# Sheet2.net
KiCad netlist of a schematic drawn in Altium Designer
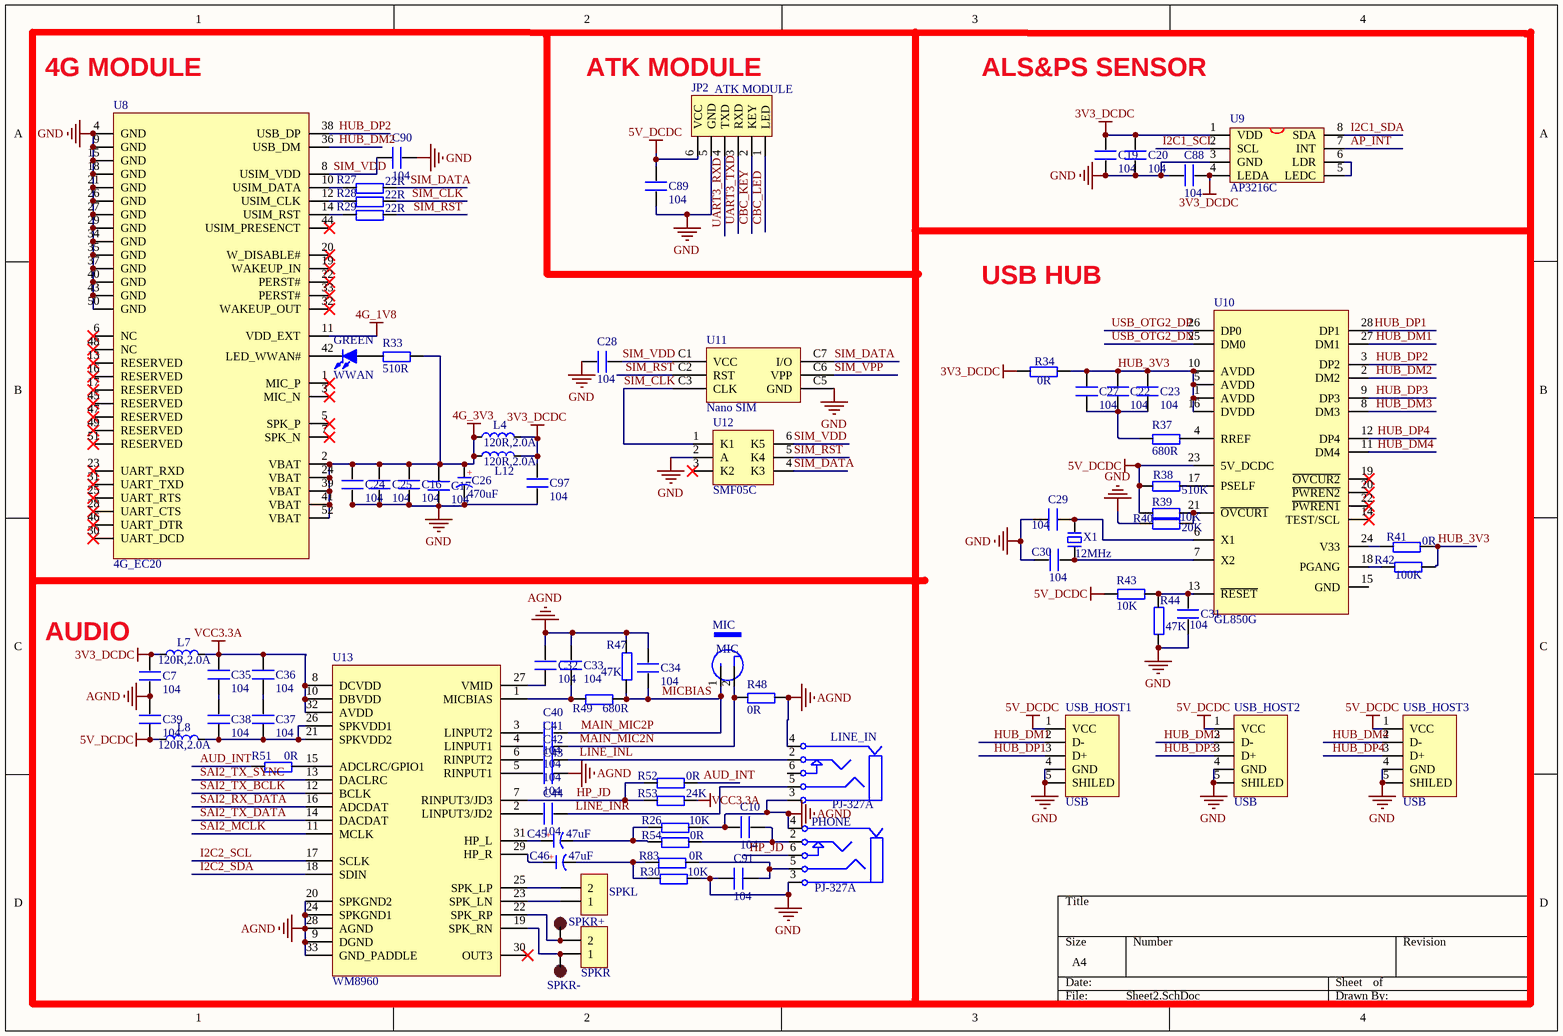
[diagram p0: Sheet2.SchDoc]

(export (version "E")
  (design (tool "Eeschema 10.0.6"))
  (components
    (comp (ref "C7") (value "104") (footprint "C 0603") (libsource (lib "linux_board_SCH") (part "C")))
    (comp (ref "C10") (value "104") (footprint "C 0603") (libsource (lib "linux_board_SCH") (part "C")))
    (comp (ref "C16") (value "104") (footprint "C 0603") (libsource (lib "linux_board_SCH") (part "C")))
    (comp (ref "C17") (value "104") (footprint "C 0603") (libsource (lib "linux_board_SCH") (part "C")))
    (comp (ref "C19") (value "104") (footprint "C 0603") (libsource (lib "linux_board_SCH") (part "C")))
    (comp (ref "C20") (value "104") (footprint "C 0603") (libsource (lib "linux_board_SCH") (part "C")))
    (comp (ref "C22") (value "104") (footprint "C 0603") (libsource (lib "linux_board_SCH") (part "C")))
    (comp (ref "C23") (value "104") (footprint "C 0603") (libsource (lib "linux_board_SCH") (part "C")))
    (comp (ref "C24") (value "104") (footprint "C 0603") (libsource (lib "linux_board_SCH") (part "C")))
    (comp (ref "C25") (value "104") (footprint "C 0603") (libsource (lib "linux_board_SCH") (part "C")))
    (comp (ref "C26")
      (value "470uF")
      (footprint "CM D(6.3*5.4)")
      (description "贴片电解电容")
      (fields (field (name "版权归属") "源创客"))
      (libsource (lib "linux_board_SCH") (part "C-CM"))
    )
    (comp (ref "C27") (value "104") (footprint "C 0603") (libsource (lib "linux_board_SCH") (part "C")))
    (comp (ref "C28") (value "104") (footprint "C 0603") (libsource (lib "linux_board_SCH") (part "C")))
    (comp (ref "C29") (value "104") (footprint "C 0603") (libsource (lib "linux_board_SCH") (part "C")))
    (comp (ref "C30") (value "104") (footprint "C 0603") (libsource (lib "linux_board_SCH") (part "C")))
    (comp (ref "C31") (value "104") (footprint "C 0603") (libsource (lib "linux_board_SCH") (part "C")))
    (comp (ref "C32") (value "104") (footprint "C 0603") (libsource (lib "linux_board_SCH") (part "C")))
    (comp (ref "C33") (value "104") (footprint "C 0603") (libsource (lib "linux_board_SCH") (part "C")))
    (comp (ref "C34") (value "104") (footprint "C 0603") (libsource (lib "linux_board_SCH") (part "C")))
    (comp (ref "C35") (value "104") (footprint "C 0603") (libsource (lib "linux_board_SCH") (part "C")))
    (comp (ref "C36") (value "104") (footprint "C 0603") (libsource (lib "linux_board_SCH") (part "C")))
    (comp (ref "C37") (value "104") (footprint "C 0603") (libsource (lib "linux_board_SCH") (part "C")))
    (comp (ref "C38") (value "104") (footprint "C 0603") (libsource (lib "linux_board_SCH") (part "C")))
    (comp (ref "C39") (value "104") (footprint "C 0603") (libsource (lib "linux_board_SCH") (part "C")))
    (comp (ref "C40") (value "104") (footprint "C 0603") (libsource (lib "linux_board_SCH") (part "C")))
    (comp (ref "C41") (value "104") (footprint "C 0603") (libsource (lib "linux_board_SCH") (part "C")))
    (comp (ref "C42") (value "104") (footprint "C 0603") (libsource (lib "linux_board_SCH") (part "C")))
    (comp (ref "C43") (value "104") (footprint "C 0603") (libsource (lib "linux_board_SCH") (part "C")))
    (comp (ref "C44") (value "104") (footprint "C 0603") (libsource (lib "linux_board_SCH") (part "C")))
    (comp (ref "C45")
      (value "47uF")
      (footprint "CM D(6.3*5.4)")
      (description "贴片电解电容")
      (fields (field (name "版权归属") "源创客"))
      (libsource (lib "") (part "C-CM_1"))
    )
    (comp (ref "C46")
      (value "47uF")
      (footprint "CM D(6.3*5.4)")
      (description "贴片电解电容")
      (fields (field (name "版权归属") "源创客"))
      (libsource (lib "") (part "C-CM_1"))
    )
    (comp (ref "C88") (value "104") (footprint "C 0603") (libsource (lib "linux_board_SCH") (part "C")))
    (comp (ref "C89") (value "104") (footprint "C 0603") (libsource (lib "linux_board_SCH") (part "C")))
    (comp (ref "C90") (value "104") (footprint "C 0603") (libsource (lib "linux_board_SCH") (part "C")))
    (comp (ref "C91") (value "104") (footprint "C 0603") (libsource (lib "linux_board_SCH") (part "C")))
    (comp (ref "C97") (value "104") (footprint "C 0603") (libsource (lib "linux_board_SCH") (part "C")))
    (comp (ref "GREEN")
      (value "WWAN")
      (footprint "LED 0805R")
      (description "贴片LED")
      (fields (field (name "版权归属") "源创客"))
      (libsource (lib "linux_board_SCH") (part "LED-SMD"))
    )
    (comp (ref "JP2")
      (value "ATK MODULE")
      (footprint "HEAD6")
      (description "ATK-HC05")
      (libsource (lib "linux_board_SCH") (part "ATK-HC05"))
    )
    (comp (ref "L4")
      (value "120R,2.0A")
      (footprint "L 0603")
      (description "小功率贴片电感磁珠")
      (fields (field (name "版权归属") "源创客"))
      (libsource (lib "linux_board_SCH") (part "L"))
    )
    (comp (ref "L7")
      (value "120R,2.0A")
      (footprint "L 0603")
      (description "小功率贴片电感磁珠")
      (fields (field (name "版权归属") "源创客"))
      (libsource (lib "linux_board_SCH") (part "L"))
    )
    (comp (ref "L8")
      (value "120R,2.0A")
      (footprint "L 0603")
      (description "小功率贴片电感磁珠")
      (fields (field (name "版权归属") "源创客"))
      (libsource (lib "linux_board_SCH") (part "L"))
    )
    (comp (ref "L12")
      (value "120R,2.0A")
      (footprint "L 0603")
      (description "小功率贴片电感磁珠")
      (fields (field (name "版权归属") "源创客"))
      (libsource (lib "linux_board_SCH") (part "L"))
    )
    (comp (ref "LINE_IN")
      (value "PJ-327A")
      (footprint "PJ327A")
      (libsource (lib "linux_board_SCH") (part "PJ-327A"))
    )
    (comp (ref "MIC") (value "MIC") (footprint "MIC-6022") (libsource (lib "linux_board_SCH") (part "MIC")))
    (comp (ref "PHONE")
      (value "PJ-327A")
      (footprint "PJ327A")
      (libsource (lib "linux_board_SCH") (part "PJ-327A"))
    )
    (comp (ref "R26") (value "10K") (footprint "R 0603") (libsource (lib "linux_board_SCH") (part "R")))
    (comp (ref "R27") (value "22R") (footprint "R 0603") (libsource (lib "linux_board_SCH") (part "R")))
    (comp (ref "R28") (value "22R") (footprint "R 0603") (libsource (lib "linux_board_SCH") (part "R")))
    (comp (ref "R29") (value "22R") (footprint "R 0603") (libsource (lib "linux_board_SCH") (part "R")))
    (comp (ref "R30") (value "10K") (footprint "R 0603") (libsource (lib "linux_board_SCH") (part "R")))
    (comp (ref "R33") (value "510R") (footprint "R 0603") (libsource (lib "linux_board_SCH") (part "R")))
    (comp (ref "R34") (value "0R") (footprint "R 0603") (libsource (lib "linux_board_SCH") (part "R")))
    (comp (ref "R37") (value "680R") (footprint "R 0603") (libsource (lib "linux_board_SCH") (part "R")))
    (comp (ref "R38") (value "510K") (footprint "R 0603") (libsource (lib "linux_board_SCH") (part "R")))
    (comp (ref "R39") (value "10K") (footprint "R 0603") (libsource (lib "linux_board_SCH") (part "R")))
    (comp (ref "R40") (value "20K") (footprint "R 0603") (libsource (lib "linux_board_SCH") (part "R")))
    (comp (ref "R41") (value "0R") (footprint "R 0603") (libsource (lib "linux_board_SCH") (part "R")))
    (comp (ref "R42") (value "100K") (footprint "R 0603") (libsource (lib "linux_board_SCH") (part "R")))
    (comp (ref "R43") (value "10K") (footprint "R 0603") (libsource (lib "linux_board_SCH") (part "R")))
    (comp (ref "R44") (value "47K") (footprint "R 0603") (libsource (lib "linux_board_SCH") (part "R")))
    (comp (ref "R47") (value "47K") (footprint "R 0603") (libsource (lib "linux_board_SCH") (part "R")))
    (comp (ref "R48") (value "0R") (footprint "R 0603") (libsource (lib "linux_board_SCH") (part "R")))
    (comp (ref "R49") (value "680R") (footprint "R 0603") (libsource (lib "linux_board_SCH") (part "R")))
    (comp (ref "R51") (value "0R") (footprint "R 0603") (libsource (lib "linux_board_SCH") (part "R")))
    (comp (ref "R52") (value "0R") (footprint "R 0603") (libsource (lib "linux_board_SCH") (part "R")))
    (comp (ref "R53") (value "24K") (footprint "R 0603") (libsource (lib "linux_board_SCH") (part "R")))
    (comp (ref "R54") (value "0R") (footprint "R 0603") (libsource (lib "linux_board_SCH") (part "R")))
    (comp (ref "R83") (value "0R") (footprint "R 0603") (libsource (lib "linux_board_SCH") (part "R")))
    (comp (ref "SPKL")
      (value "SPKL")
      (footprint "XH2.54-2P_H")
      (description "2P接插件")
      (fields (field (name "版权归属") "源创客"))
      (libsource (lib "linux_board_SCH") (part "Header 2"))
    )
    (comp (ref "SPKR")
      (value "SPKL")
      (footprint "XH2.54-2P_H")
      (description "2P接插件")
      (fields (field (name "版权归属") "源创客"))
      (libsource (lib "linux_board_SCH") (part "Header 2"))
    )
    (comp (ref "SPKR+")
      (value "SPK+")
      (footprint "TP-1.5")
      (description "测试点")
      (libsource (lib "linux_board_SCH") (part "TEST-POINT"))
    )
    (comp (ref "SPKR-")
      (value "SPK+")
      (footprint "TP-1.5")
      (description "测试点")
      (libsource (lib "linux_board_SCH") (part "TEST-POINT"))
    )
    (comp (ref "U8")
      (value "4G_EC20")
      (footprint "Mini PCIE 52P")
      (libsource (lib "linux_board_SCH") (part "4G-EC20"))
    )
    (comp (ref "U9")
      (value "AP3216C")
      (footprint "QFN8")
      (description "ALS+PS Sensor")
      (libsource (lib "linux_board_SCH") (part "AP3216C"))
    )
    (comp (ref "U10")
      (value "GL850G")
      (footprint "SSOP28_L")
      (libsource (lib "linux_board_SCH") (part "GL850G"))
    )
    (comp (ref "U11")
      (value "Nano SIM")
      (footprint "Nano SIM 7P")
      (libsource (lib "linux_board_SCH") (part "Nano SIM"))
    )
    (comp (ref "U12")
      (value "SMF05C")
      (footprint "SOT363-6L")
      (libsource (lib "linux_board_SCH") (part "SMF05C"))
    )
    (comp (ref "U13")
      (value "WM8960")
      (footprint "QFN32 5x5_L")
      (libsource (lib "linux_board_SCH") (part "WM8960"))
    )
    (comp (ref "USB_HOST1")
      (value "USB")
      (footprint "USB-A/S_E")
      (description "USB-A型母接口")
      (fields (field (name "版权归属") "源创客"))
      (libsource (lib "linux_board_SCH") (part "USB-A/S"))
    )
    (comp (ref "USB_HOST2")
      (value "USB")
      (footprint "USB-A/S_E")
      (description "USB-A型母接口")
      (fields (field (name "版权归属") "源创客"))
      (libsource (lib "linux_board_SCH") (part "USB-A/S"))
    )
    (comp (ref "USB_HOST3")
      (value "USB")
      (footprint "USB-A/S_E")
      (description "USB-A型母接口")
      (fields (field (name "版权归属") "源创客"))
      (libsource (lib "linux_board_SCH") (part "USB-A/S"))
    )
    (comp (ref "X1")
      (value "12MHz")
      (footprint "XTAL-49S DIP")
      (description "2脚无源晶振")
      (fields (field (name "版权归属") "源创客"))
      (libsource (lib "linux_board_SCH") (part "XTAL-2P"))
    )
  )
  (nets
    (net (code "1") (name "/AP_INT") (class "Default")
      (node (ref "U9") (pin "7") (pinfunction "INT_7") (pintype "passive"))
    )
    (net (code "2") (name "/AUD_INT") (class "Default")
      (node (ref "R51") (pin "1") (pintype "passive"))
      (node (ref "R52") (pin "2") (pintype "passive"))
    )
    (net (code "3") (name "/CBC_KEY") (class "Default")
      (node (ref "JP2") (pin "2") (pinfunction "KEY_2") (pintype "passive"))
    )
    (net (code "4") (name "/CBC_LED") (class "Default")
      (node (ref "JP2") (pin "1") (pinfunction "LED_1") (pintype "passive"))
    )
    (net (code "5") (name "/HP_JD") (class "Default")
      (node (ref "PHONE") (pin "6") (pinfunction "6_6") (pintype "passive"))
      (node (ref "R52") (pin "1") (pintype "passive"))
      (node (ref "R53") (pin "1") (pintype "passive"))
      (node (ref "U13") (pin "7") (pinfunction "RINPUT3/JD3_7") (pintype "passive"))
    )
    (net (code "6") (name "/HUB_3V3") (class "Default")
      (node (ref "C22") (pin "2") (pinfunction "2_2") (pintype "passive"))
      (node (ref "C23") (pin "2") (pinfunction "2_2") (pintype "passive"))
      (node (ref "C27") (pin "2") (pinfunction "2_2") (pintype "passive"))
      (node (ref "R34") (pin "2") (pintype "passive"))
      (node (ref "R41") (pin "2") (pintype "passive"))
      (node (ref "R42") (pin "2") (pintype "passive"))
      (node (ref "U10") (pin "1") (pinfunction "AVDD_1") (pintype "passive"))
      (node (ref "U10") (pin "10") (pinfunction "AVDD_10") (pintype "passive"))
      (node (ref "U10") (pin "16") (pinfunction "DVDD_16") (pintype "passive"))
      (node (ref "U10") (pin "5") (pinfunction "AVDD_5") (pintype "passive"))
    )
    (net (code "7") (name "/HUB_DM1") (class "Default")
      (node (ref "U10") (pin "27") (pinfunction "DM1_27") (pintype "passive"))
      (node (ref "USB_HOST1") (pin "2") (pinfunction "D-_2") (pintype "passive"))
    )
    (net (code "8") (name "/HUB_DM2") (class "Default")
      (node (ref "U10") (pin "2") (pinfunction "DM2_2") (pintype "passive"))
      (node (ref "U8") (pin "36") (pinfunction "USB_DM_36") (pintype "passive"))
    )
    (net (code "9") (name "/HUB_DM3") (class "Default")
      (node (ref "U10") (pin "8") (pinfunction "DM3_8") (pintype "passive"))
      (node (ref "USB_HOST2") (pin "2") (pinfunction "D-_2") (pintype "passive"))
    )
    (net (code "10") (name "/HUB_DM4") (class "Default")
      (node (ref "U10") (pin "11") (pinfunction "DM4_11") (pintype "passive"))
      (node (ref "USB_HOST3") (pin "2") (pinfunction "D-_2") (pintype "passive"))
    )
    (net (code "11") (name "/HUB_DP1") (class "Default")
      (node (ref "U10") (pin "28") (pinfunction "DP1_28") (pintype "passive"))
      (node (ref "USB_HOST1") (pin "3") (pinfunction "D+_3") (pintype "passive"))
    )
    (net (code "12") (name "/HUB_DP2") (class "Default")
      (node (ref "U10") (pin "3") (pinfunction "DP2_3") (pintype "passive"))
      (node (ref "U8") (pin "38") (pinfunction "USB_DP_38") (pintype "passive"))
    )
    (net (code "13") (name "/HUB_DP3") (class "Default")
      (node (ref "U10") (pin "9") (pinfunction "DP3_9") (pintype "passive"))
      (node (ref "USB_HOST2") (pin "3") (pinfunction "D+_3") (pintype "passive"))
    )
    (net (code "14") (name "/HUB_DP4") (class "Default")
      (node (ref "U10") (pin "12") (pinfunction "DP4_12") (pintype "passive"))
      (node (ref "USB_HOST3") (pin "3") (pinfunction "D+_3") (pintype "passive"))
    )
    (net (code "15") (name "/I2C1_SCL") (class "Default")
      (node (ref "U9") (pin "2") (pinfunction "SCL_2") (pintype "passive"))
    )
    (net (code "16") (name "/I2C1_SDA") (class "Default")
      (node (ref "U9") (pin "8") (pinfunction "SDA_8") (pintype "passive"))
    )
    (net (code "17") (name "/I2C2_SCL") (class "Default")
      (node (ref "U13") (pin "17") (pinfunction "SCLK_17") (pintype "passive"))
    )
    (net (code "18") (name "/I2C2_SDA") (class "Default")
      (node (ref "U13") (pin "18") (pinfunction "SDIN_18") (pintype "passive"))
    )
    (net (code "19") (name "/LINE_INL") (class "Default")
      (node (ref "C42") (pin "2") (pinfunction "2_2") (pintype "passive"))
      (node (ref "LINE_IN") (pin "2") (pinfunction "2_2") (pintype "passive"))
    )
    (net (code "20") (name "/LINE_INR") (class "Default")
      (node (ref "C44") (pin "2") (pinfunction "2_2") (pintype "passive"))
      (node (ref "LINE_IN") (pin "5") (pinfunction "5_5") (pintype "passive"))
    )
    (net (code "21") (name "/MAIN_MIC2N") (class "Default")
      (node (ref "C41") (pin "2") (pinfunction "2_2") (pintype "passive"))
      (node (ref "MIC") (pin "2") (pinfunction "GND_2") (pintype "passive"))
      (node (ref "R48") (pin "1") (pintype "passive"))
    )
    (net (code "22") (name "/MAIN_MIC2P") (class "Default")
      (node (ref "C34") (pin "1") (pinfunction "1_1") (pintype "passive"))
      (node (ref "C40") (pin "2") (pinfunction "2_2") (pintype "passive"))
      (node (ref "MIC") (pin "1") (pinfunction "VCC_1") (pintype "passive"))
      (node (ref "R47") (pin "1") (pintype "passive"))
      (node (ref "R49") (pin "2") (pintype "passive"))
    )
    (net (code "23") (name "/SAI2_MCLK") (class "Default")
      (node (ref "U13") (pin "11") (pinfunction "MCLK_11") (pintype "passive"))
    )
    (net (code "24") (name "/SAI2_RX_DATA") (class "Default")
      (node (ref "U13") (pin "16") (pinfunction "ADCDAT_16") (pintype "passive"))
    )
    (net (code "25") (name "/SAI2_TX_BCLK") (class "Default")
      (node (ref "U13") (pin "12") (pinfunction "BCLK_12") (pintype "passive"))
    )
    (net (code "26") (name "/SAI2_TX_DATA") (class "Default")
      (node (ref "U13") (pin "14") (pinfunction "DACDAT_14") (pintype "passive"))
    )
    (net (code "27") (name "/SAI2_TX_SYNC") (class "Default")
      (node (ref "U13") (pin "13") (pinfunction "DACLRC_13") (pintype "passive"))
    )
    (net (code "28") (name "/SIM_CLK") (class "Default")
      (node (ref "R28") (pin "2") (pintype "passive"))
      (node (ref "U11") (pin "C3") (pinfunction "CLK_C3") (pintype "passive"))
      (node (ref "U12") (pin "1") (pinfunction "K1_1") (pintype "passive"))
    )
    (net (code "29") (name "/SIM_DATA") (class "Default")
      (node (ref "R27") (pin "2") (pintype "passive"))
      (node (ref "U11") (pin "C7") (pinfunction "I/O_C7") (pintype "passive"))
      (node (ref "U12") (pin "4") (pinfunction "K3_4") (pintype "passive"))
    )
    (net (code "30") (name "/SIM_RST") (class "Default")
      (node (ref "R29") (pin "2") (pintype "passive"))
      (node (ref "U11") (pin "C2") (pinfunction "RST_C2") (pintype "passive"))
      (node (ref "U12") (pin "5") (pinfunction "K4_5") (pintype "passive"))
    )
    (net (code "31") (name "/SIM_VDD") (class "Default")
      (node (ref "C28") (pin "1") (pinfunction "1_1") (pintype "passive"))
      (node (ref "C90") (pin "1") (pinfunction "1_1") (pintype "passive"))
      (node (ref "U11") (pin "C1") (pinfunction "VCC_C1") (pintype "passive"))
      (node (ref "U12") (pin "6") (pinfunction "K5_6") (pintype "passive"))
      (node (ref "U8") (pin "8") (pinfunction "USIM_VDD_8") (pintype "passive"))
    )
    (net (code "32") (name "/SIM_VPP") (class "Default")
      (node (ref "U11") (pin "C6") (pinfunction "VPP_C6") (pintype "passive"))
    )
    (net (code "33") (name "/UART3_RXD") (class "Default")
      (node (ref "JP2") (pin "4") (pinfunction "TXD_4") (pintype "passive"))
    )
    (net (code "34") (name "/UART3_TXD") (class "Default")
      (node (ref "JP2") (pin "3") (pinfunction "RXD_3") (pintype "passive"))
    )
    (net (code "35") (name "/USB_OTG2_DN") (class "Default")
      (node (ref "U10") (pin "25") (pinfunction "DM0_25") (pintype "passive"))
    )
    (net (code "36") (name "/USB_OTG2_DP") (class "Default")
      (node (ref "U10") (pin "26") (pinfunction "DP0_26") (pintype "passive"))
    )
    (net (code "37") (name "3V3_DCDC") (class "Default")
      (node (ref "C19") (pin "2") (pinfunction "2_2") (pintype "passive"))
      (node (ref "C20") (pin "2") (pinfunction "2_2") (pintype "passive"))
      (node (ref "C7") (pin "2") (pinfunction "2_2") (pintype "passive"))
      (node (ref "C88") (pin "1") (pinfunction "1_1") (pintype "passive"))
      (node (ref "C97") (pin "2") (pinfunction "2_2") (pintype "passive"))
      (node (ref "L12") (pin "2") (pinfunction "2_2") (pintype "passive"))
      (node (ref "L4") (pin "2") (pinfunction "2_2") (pintype "passive"))
      (node (ref "L7") (pin "1") (pinfunction "1_1") (pintype "passive"))
      (node (ref "R34") (pin "1") (pintype "passive"))
      (node (ref "U9") (pin "1") (pinfunction "VDD_1") (pintype "passive"))
      (node (ref "U9") (pin "4") (pinfunction "LEDA_4") (pintype "passive"))
    )
    (net (code "38") (name "4G_1V8") (class "Default")
      (node (ref "U8") (pin "11") (pinfunction "VDD_EXT_11") (pintype "passive"))
    )
    (net (code "39") (name "4G_3V3") (class "Default")
      (node (ref "C16") (pin "2") (pinfunction "2_2") (pintype "passive"))
      (node (ref "C17") (pin "2") (pinfunction "2_2") (pintype "passive"))
      (node (ref "C24") (pin "2") (pinfunction "2_2") (pintype "passive"))
      (node (ref "C25") (pin "2") (pinfunction "2_2") (pintype "passive"))
      (node (ref "C26") (pin "1") (pinfunction "A_1") (pintype "passive"))
      (node (ref "L12") (pin "1") (pinfunction "1_1") (pintype "passive"))
      (node (ref "L4") (pin "1") (pinfunction "1_1") (pintype "passive"))
      (node (ref "R33") (pin "2") (pintype "passive"))
      (node (ref "U8") (pin "2") (pinfunction "VBAT_2") (pintype "passive"))
      (node (ref "U8") (pin "24") (pinfunction "VBAT_24") (pintype "passive"))
      (node (ref "U8") (pin "39") (pinfunction "VBAT_39") (pintype "passive"))
      (node (ref "U8") (pin "41") (pinfunction "VBAT_41") (pintype "passive"))
      (node (ref "U8") (pin "52") (pinfunction "VBAT_52") (pintype "passive"))
    )
    (net (code "40") (name "5V_DCDC") (class "Default")
      (node (ref "C39") (pin "1") (pinfunction "1_1") (pintype "passive"))
      (node (ref "C89") (pin "1") (pinfunction "1_1") (pintype "passive"))
      (node (ref "JP2") (pin "6") (pinfunction "VCC_6") (pintype "passive"))
      (node (ref "L8") (pin "1") (pinfunction "1_1") (pintype "passive"))
      (node (ref "R38") (pin "1") (pintype "passive"))
      (node (ref "R39") (pin "1") (pintype "passive"))
      (node (ref "R43") (pin "1") (pintype "passive"))
      (node (ref "U10") (pin "23") (pinfunction "5V_DCDC_23") (pintype "passive"))
      (node (ref "USB_HOST1") (pin "1") (pinfunction "VCC_1") (pintype "passive"))
      (node (ref "USB_HOST2") (pin "1") (pinfunction "VCC_1") (pintype "passive"))
      (node (ref "USB_HOST3") (pin "1") (pinfunction "VCC_1") (pintype "passive"))
    )
    (net (code "41") (name "AGND") (class "Default")
      (node (ref "C10") (pin "1") (pinfunction "1_1") (pintype "passive"))
      (node (ref "C32") (pin "1") (pinfunction "1_1") (pintype "passive"))
      (node (ref "C33") (pin "2") (pinfunction "2_2") (pintype "passive"))
      (node (ref "C34") (pin "2") (pinfunction "2_2") (pintype "passive"))
      (node (ref "C39") (pin "2") (pinfunction "2_2") (pintype "passive"))
      (node (ref "C43") (pin "2") (pinfunction "2_2") (pintype "passive"))
      (node (ref "C7") (pin "1") (pinfunction "1_1") (pintype "passive"))
      (node (ref "LINE_IN") (pin "3") (pinfunction "1_3") (pintype "passive"))
      (node (ref "LINE_IN") (pin "4") (pinfunction "4_4") (pintype "passive"))
      (node (ref "PHONE") (pin "4") (pinfunction "4_4") (pintype "passive"))
      (node (ref "R26") (pin "2") (pintype "passive"))
      (node (ref "R47") (pin "2") (pintype "passive"))
      (node (ref "R48") (pin "2") (pintype "passive"))
      (node (ref "U13") (pin "20") (pinfunction "SPKGND2_20") (pintype "passive"))
      (node (ref "U13") (pin "24") (pinfunction "SPKGND1_24") (pintype "passive"))
      (node (ref "U13") (pin "28") (pinfunction "AGND_28") (pintype "passive"))
      (node (ref "U13") (pin "33") (pinfunction "GND_PADDLE_33") (pintype "passive"))
      (node (ref "U13") (pin "9") (pinfunction "DGND_9") (pintype "passive"))
    )
    (net (code "42") (name "GND") (class "Default")
      (node (ref "C16") (pin "1") (pinfunction "1_1") (pintype "passive"))
      (node (ref "C17") (pin "1") (pinfunction "1_1") (pintype "passive"))
      (node (ref "C19") (pin "1") (pinfunction "1_1") (pintype "passive"))
      (node (ref "C20") (pin "1") (pinfunction "1_1") (pintype "passive"))
      (node (ref "C24") (pin "1") (pinfunction "1_1") (pintype "passive"))
      (node (ref "C25") (pin "1") (pinfunction "1_1") (pintype "passive"))
      (node (ref "C26") (pin "2") (pinfunction "K_2") (pintype "passive"))
      (node (ref "C28") (pin "2") (pinfunction "2_2") (pintype "passive"))
      (node (ref "C29") (pin "2") (pinfunction "2_2") (pintype "passive"))
      (node (ref "C30") (pin "2") (pinfunction "2_2") (pintype "passive"))
      (node (ref "C31") (pin "2") (pinfunction "2_2") (pintype "passive"))
      (node (ref "C88") (pin "2") (pinfunction "2_2") (pintype "passive"))
      (node (ref "C89") (pin "2") (pinfunction "2_2") (pintype "passive"))
      (node (ref "C90") (pin "2") (pinfunction "2_2") (pintype "passive"))
      (node (ref "C91") (pin "1") (pinfunction "1_1") (pintype "passive"))
      (node (ref "C97") (pin "1") (pinfunction "1_1") (pintype "passive"))
      (node (ref "JP2") (pin "5") (pinfunction "GND_5") (pintype "passive"))
      (node (ref "PHONE") (pin "3") (pinfunction "1_3") (pintype "passive"))
      (node (ref "R30") (pin "2") (pintype "passive"))
      (node (ref "R40") (pin "1") (pintype "passive"))
      (node (ref "R44") (pin "1") (pintype "passive"))
      (node (ref "U11") (pin "C5") (pinfunction "GND_C5") (pintype "passive"))
      (node (ref "U12") (pin "2") (pinfunction "A_2") (pintype "passive"))
      (node (ref "U8") (pin "15") (pinfunction "GND_15") (pintype "passive"))
      (node (ref "U8") (pin "18") (pinfunction "GND_18") (pintype "passive"))
      (node (ref "U8") (pin "21") (pinfunction "GND_21") (pintype "passive"))
      (node (ref "U8") (pin "26") (pinfunction "GND_26") (pintype "passive"))
      (node (ref "U8") (pin "27") (pinfunction "GND_27") (pintype "passive"))
      (node (ref "U8") (pin "29") (pinfunction "GND_29") (pintype "passive"))
      (node (ref "U8") (pin "34") (pinfunction "GND_34") (pintype "passive"))
      (node (ref "U8") (pin "35") (pinfunction "GND_35") (pintype "passive"))
      (node (ref "U8") (pin "37") (pinfunction "GND_37") (pintype "passive"))
      (node (ref "U8") (pin "4") (pinfunction "GND_4") (pintype "passive"))
      (node (ref "U8") (pin "40") (pinfunction "GND_40") (pintype "passive"))
      (node (ref "U8") (pin "43") (pinfunction "GND_43") (pintype "passive"))
      (node (ref "U8") (pin "50") (pinfunction "GND_50") (pintype "passive"))
      (node (ref "U8") (pin "9") (pinfunction "GND_9") (pintype "passive"))
      (node (ref "U9") (pin "3") (pinfunction "GND_3") (pintype "passive"))
      (node (ref "USB_HOST1") (pin "4") (pinfunction "GND_4") (pintype "passive"))
      (node (ref "USB_HOST1") (pin "5") (pinfunction "SHILED_5") (pintype "passive"))
      (node (ref "USB_HOST2") (pin "4") (pinfunction "GND_4") (pintype "passive"))
      (node (ref "USB_HOST2") (pin "5") (pinfunction "SHILED_5") (pintype "passive"))
      (node (ref "USB_HOST3") (pin "4") (pinfunction "GND_4") (pintype "passive"))
      (node (ref "USB_HOST3") (pin "5") (pinfunction "SHILED_5") (pintype "passive"))
    )
    (net (code "43") (name "Net-(C10-Pad2)") (class "Default")
      (node (ref "C10") (pin "2") (pinfunction "2_2") (pintype "passive"))
      (node (ref "PHONE") (pin "2") (pinfunction "2_2") (pintype "passive"))
      (node (ref "R54") (pin "2") (pintype "passive"))
    )
    (net (code "44") (name "Net-(C22-Pad1)") (class "Default")
      (node (ref "C22") (pin "1") (pinfunction "1_1") (pintype "passive"))
      (node (ref "C23") (pin "1") (pinfunction "1_1") (pintype "passive"))
      (node (ref "C27") (pin "1") (pinfunction "1_1") (pintype "passive"))
      (node (ref "R37") (pin "1") (pintype "passive"))
    )
    (net (code "45") (name "Net-(C35-Pad1)") (class "Default")
      (node (ref "C35") (pin "1") (pinfunction "1_1") (pintype "passive"))
      (node (ref "C38") (pin "2") (pinfunction "2_2") (pintype "passive"))
    )
    (net (code "46") (name "Net-(C36-Pad1)") (class "Default")
      (node (ref "C36") (pin "1") (pinfunction "1_1") (pintype "passive"))
      (node (ref "C37") (pin "2") (pinfunction "2_2") (pintype "passive"))
    )
    (net (code "47") (name "Net-(C45-A)") (class "Default")
      (node (ref "C45") (pin "1") (pinfunction "A_1") (pintype "passive"))
      (node (ref "U13") (pin "31") (pinfunction "HP_L_31") (pintype "passive"))
    )
    (net (code "48") (name "Net-(C45-K)") (class "Default")
      (node (ref "C45") (pin "2") (pinfunction "K_2") (pintype "passive"))
      (node (ref "R26") (pin "1") (pintype "passive"))
      (node (ref "R54") (pin "1") (pintype "passive"))
    )
    (net (code "49") (name "Net-(C46-A)") (class "Default")
      (node (ref "C46") (pin "1") (pinfunction "A_1") (pintype "passive"))
      (node (ref "U13") (pin "29") (pinfunction "HP_R_29") (pintype "passive"))
    )
    (net (code "50") (name "Net-(C46-K)") (class "Default")
      (node (ref "C46") (pin "2") (pinfunction "K_2") (pintype "passive"))
      (node (ref "R30") (pin "1") (pintype "passive"))
      (node (ref "R83") (pin "1") (pintype "passive"))
    )
    (net (code "51") (name "Net-(C91-Pad2)") (class "Default")
      (node (ref "C91") (pin "2") (pinfunction "2_2") (pintype "passive"))
      (node (ref "PHONE") (pin "5") (pinfunction "5_5") (pintype "passive"))
      (node (ref "R83") (pin "2") (pintype "passive"))
    )
    (net (code "52") (name "Net-(GREEN-A)") (class "Default")
      (node (ref "GREEN") (pin "1") (pinfunction "A_1") (pintype "passive"))
      (node (ref "R33") (pin "1") (pintype "passive"))
    )
    (net (code "53") (name "Net-(GREEN-K)") (class "Default")
      (node (ref "GREEN") (pin "2") (pinfunction "K_2") (pintype "passive"))
      (node (ref "U8") (pin "42") (pinfunction "LED_WWAN#_42") (pintype "passive"))
    )
    (net (code "54") (name "Net-(U8-USIM_CLK)") (class "Default")
      (node (ref "R28") (pin "1") (pintype "passive"))
      (node (ref "U8") (pin "12") (pinfunction "USIM_CLK_12") (pintype "passive"))
    )
    (net (code "55") (name "Net-(U8-USIM_DATA)") (class "Default")
      (node (ref "R27") (pin "1") (pintype "passive"))
      (node (ref "U8") (pin "10") (pinfunction "USIM_DATA_10") (pintype "passive"))
    )
    (net (code "56") (name "Net-(U8-USIM_RST)") (class "Default")
      (node (ref "R29") (pin "1") (pintype "passive"))
      (node (ref "U8") (pin "14") (pinfunction "USIM_RST_14") (pintype "passive"))
    )
    (net (code "57") (name "Net-(U9-LDR)") (class "Default")
      (node (ref "U9") (pin "5") (pinfunction "LEDC_5") (pintype "passive"))
      (node (ref "U9") (pin "6") (pinfunction "LDR_6") (pintype "passive"))
    )
    (net (code "58") (name "Net-(U10-PGANG)") (class "Default")
      (node (ref "R42") (pin "1") (pintype "passive"))
      (node (ref "U10") (pin "18") (pinfunction "PGANG_18") (pintype "passive"))
    )
    (net (code "59") (name "Net-(U10-PSELF)") (class "Default")
      (node (ref "R38") (pin "2") (pintype "passive"))
      (node (ref "U10") (pin "17") (pinfunction "PSELF_17") (pintype "passive"))
    )
    (net (code "60") (name "Net-(U10-RREF)") (class "Default")
      (node (ref "R37") (pin "2") (pintype "passive"))
      (node (ref "U10") (pin "4") (pinfunction "RREF_4") (pintype "passive"))
    )
    (net (code "61") (name "Net-(U10-V33)") (class "Default")
      (node (ref "R41") (pin "1") (pintype "passive"))
      (node (ref "U10") (pin "24") (pinfunction "V33_24") (pintype "passive"))
    )
    (net (code "62") (name "Net-(U10-X1)") (class "Default")
      (node (ref "C29") (pin "1") (pinfunction "1_1") (pintype "passive"))
      (node (ref "U10") (pin "6") (pinfunction "X1_6") (pintype "passive"))
      (node (ref "X1") (pin "2") (pinfunction "2_2") (pintype "passive"))
    )
    (net (code "63") (name "Net-(U10-X2)") (class "Default")
      (node (ref "C30") (pin "1") (pinfunction "1_1") (pintype "passive"))
      (node (ref "U10") (pin "7") (pinfunction "X2_7") (pintype "passive"))
      (node (ref "X1") (pin "1") (pinfunction "1_1") (pintype "passive"))
    )
    (net (code "64") (name "Net-(U10-~{OVCUR1})") (class "Default")
      (node (ref "R39") (pin "2") (pintype "passive"))
      (node (ref "R40") (pin "2") (pintype "passive"))
      (node (ref "U10") (pin "21") (pinfunction "~{OVCUR1}_21") (pintype "passive"))
    )
    (net (code "65") (name "Net-(U10-~{RESET})") (class "Default")
      (node (ref "C31") (pin "1") (pinfunction "1_1") (pintype "passive"))
      (node (ref "R43") (pin "2") (pintype "passive"))
      (node (ref "R44") (pin "2") (pintype "passive"))
      (node (ref "U10") (pin "13") (pinfunction "~{RESET}_13") (pintype "passive"))
    )
    (net (code "66") (name "Net-(U13-ADCLRC{slash}GPIO1)") (class "Default")
      (node (ref "R51") (pin "2") (pintype "passive"))
      (node (ref "U13") (pin "15") (pinfunction "ADCLRC/GPIO1_15") (pintype "passive"))
    )
    (net (code "67") (name "Net-(U13-LINPUT1)") (class "Default")
      (node (ref "C41") (pin "1") (pinfunction "1_1") (pintype "passive"))
      (node (ref "U13") (pin "4") (pinfunction "LINPUT1_4") (pintype "passive"))
    )
    (net (code "68") (name "Net-(U13-LINPUT2)") (class "Default")
      (node (ref "C40") (pin "1") (pinfunction "1_1") (pintype "passive"))
      (node (ref "U13") (pin "3") (pinfunction "LINPUT2_3") (pintype "passive"))
    )
    (net (code "69") (name "Net-(U13-LINPUT3{slash}JD2)") (class "Default")
      (node (ref "C44") (pin "1") (pinfunction "1_1") (pintype "passive"))
      (node (ref "U13") (pin "2") (pinfunction "LINPUT3/JD2_2") (pintype "passive"))
    )
    (net (code "70") (name "Net-(U13-MICBIAS)") (class "Default")
      (node (ref "C33") (pin "1") (pinfunction "1_1") (pintype "passive"))
      (node (ref "R49") (pin "1") (pintype "passive"))
      (node (ref "U13") (pin "1") (pinfunction "MICBIAS_1") (pintype "passive"))
    )
    (net (code "71") (name "Net-(U13-RINPUT1)") (class "Default")
      (node (ref "C43") (pin "1") (pinfunction "1_1") (pintype "passive"))
      (node (ref "U13") (pin "5") (pinfunction "RINPUT1_5") (pintype "passive"))
    )
    (net (code "72") (name "Net-(U13-RINPUT2)") (class "Default")
      (node (ref "C42") (pin "1") (pinfunction "1_1") (pintype "passive"))
      (node (ref "U13") (pin "6") (pinfunction "RINPUT2_6") (pintype "passive"))
    )
    (net (code "73") (name "Net-(U13-SPKVDD1)") (class "Default")
      (node (ref "C37") (pin "1") (pinfunction "1_1") (pintype "passive"))
      (node (ref "C38") (pin "1") (pinfunction "1_1") (pintype "passive"))
      (node (ref "L8") (pin "2") (pinfunction "2_2") (pintype "passive"))
      (node (ref "U13") (pin "21") (pinfunction "SPKVDD2_21") (pintype "passive"))
      (node (ref "U13") (pin "26") (pinfunction "SPKVDD1_26") (pintype "passive"))
    )
    (net (code "74") (name "Net-(U13-SPK_LN)") (class "Default")
      (node (ref "SPKL") (pin "1") (pinfunction "1_1") (pintype "passive"))
      (node (ref "U13") (pin "23") (pinfunction "SPK_LN_23") (pintype "passive"))
    )
    (net (code "75") (name "Net-(U13-SPK_LP)") (class "Default")
      (node (ref "SPKL") (pin "2") (pinfunction "2_2") (pintype "passive"))
      (node (ref "U13") (pin "25") (pinfunction "SPK_LP_25") (pintype "passive"))
    )
    (net (code "76") (name "Net-(U13-SPK_RN)") (class "Default")
      (node (ref "SPKR") (pin "1") (pinfunction "1_1") (pintype "passive"))
      (node (ref "SPKR-") (pin "1") (pinfunction "1_1") (pintype "passive"))
      (node (ref "U13") (pin "19") (pinfunction "SPK_RN_19") (pintype "passive"))
    )
    (net (code "77") (name "Net-(U13-SPK_RP)") (class "Default")
      (node (ref "SPKR") (pin "2") (pinfunction "2_2") (pintype "passive"))
      (node (ref "SPKR+") (pin "1") (pinfunction "1_1") (pintype "passive"))
      (node (ref "U13") (pin "22") (pinfunction "SPK_RP_22") (pintype "passive"))
    )
    (net (code "78") (name "Net-(U13-VMID)") (class "Default")
      (node (ref "C32") (pin "2") (pinfunction "2_2") (pintype "passive"))
      (node (ref "U13") (pin "27") (pinfunction "VMID_27") (pintype "passive"))
    )
    (net (code "79") (name "VCC3.3A") (class "Default")
      (node (ref "C35") (pin "2") (pinfunction "2_2") (pintype "passive"))
      (node (ref "C36") (pin "2") (pinfunction "2_2") (pintype "passive"))
      (node (ref "L7") (pin "2") (pinfunction "2_2") (pintype "passive"))
      (node (ref "R53") (pin "2") (pintype "passive"))
      (node (ref "U13") (pin "10") (pinfunction "DBVDD_10") (pintype "passive"))
      (node (ref "U13") (pin "32") (pinfunction "AVDD_32") (pintype "passive"))
      (node (ref "U13") (pin "8") (pinfunction "DCVDD_8") (pintype "passive"))
    )
    (net (code "80") (name "unconnected-(LINE_IN-Pad6)") (class "Default")
      (node (ref "LINE_IN") (pin "6") (pinfunction "6_6") (pintype "passive"))
    )
    (net (code "81") (name "unconnected-(U8-MIC_N-Pad3)") (class "Default")
      (node (ref "U8") (pin "3") (pinfunction "MIC_N_3") (pintype "passive+no_connect"))
    )
    (net (code "82") (name "unconnected-(U8-MIC_P-Pad1)") (class "Default")
      (node (ref "U8") (pin "1") (pinfunction "MIC_P_1") (pintype "passive+no_connect"))
    )
    (net (code "83") (name "unconnected-(U8-NC-Pad6)") (class "Default")
      (node (ref "U8") (pin "6") (pinfunction "NC_6") (pintype "passive+no_connect"))
    )
    (net (code "84") (name "unconnected-(U8-NC-Pad48)") (class "Default")
      (node (ref "U8") (pin "48") (pinfunction "NC_48") (pintype "passive+no_connect"))
    )
    (net (code "85") (name "unconnected-(U8-PERST#-Pad22)") (class "Default")
      (node (ref "U8") (pin "22") (pinfunction "PERST#_22") (pintype "passive+no_connect"))
    )
    (net (code "86") (name "unconnected-(U8-PERST#-Pad33)") (class "Default")
      (node (ref "U8") (pin "33") (pinfunction "PERST#_33") (pintype "passive+no_connect"))
    )
    (net (code "87") (name "unconnected-(U8-RESERVED-Pad13)") (class "Default")
      (node (ref "U8") (pin "13") (pinfunction "RESERVED_13") (pintype "passive+no_connect"))
    )
    (net (code "88") (name "unconnected-(U8-RESERVED-Pad16)") (class "Default")
      (node (ref "U8") (pin "16") (pinfunction "RESERVED_16") (pintype "passive+no_connect"))
    )
    (net (code "89") (name "unconnected-(U8-RESERVED-Pad17)") (class "Default")
      (node (ref "U8") (pin "17") (pinfunction "RESERVED_17") (pintype "passive+no_connect"))
    )
    (net (code "90") (name "unconnected-(U8-RESERVED-Pad45)") (class "Default")
      (node (ref "U8") (pin "45") (pinfunction "RESERVED_45") (pintype "passive+no_connect"))
    )
    (net (code "91") (name "unconnected-(U8-RESERVED-Pad47)") (class "Default")
      (node (ref "U8") (pin "47") (pinfunction "RESERVED_47") (pintype "passive+no_connect"))
    )
    (net (code "92") (name "unconnected-(U8-RESERVED-Pad49)") (class "Default")
      (node (ref "U8") (pin "49") (pinfunction "RESERVED_49") (pintype "passive+no_connect"))
    )
    (net (code "93") (name "unconnected-(U8-RESERVED-Pad51)") (class "Default")
      (node (ref "U8") (pin "51") (pinfunction "RESERVED_51") (pintype "passive+no_connect"))
    )
    (net (code "94") (name "unconnected-(U8-SPK_N-Pad7)") (class "Default")
      (node (ref "U8") (pin "7") (pinfunction "SPK_N_7") (pintype "passive+no_connect"))
    )
    (net (code "95") (name "unconnected-(U8-SPK_P-Pad5)") (class "Default")
      (node (ref "U8") (pin "5") (pinfunction "SPK_P_5") (pintype "passive+no_connect"))
    )
    (net (code "96") (name "unconnected-(U8-UART_CTS-Pad28)") (class "Default")
      (node (ref "U8") (pin "28") (pinfunction "UART_CTS_28") (pintype "passive+no_connect"))
    )
    (net (code "97") (name "unconnected-(U8-UART_DCD-Pad30)") (class "Default")
      (node (ref "U8") (pin "30") (pinfunction "UART_DCD_30") (pintype "passive+no_connect"))
    )
    (net (code "98") (name "unconnected-(U8-UART_DTR-Pad46)") (class "Default")
      (node (ref "U8") (pin "46") (pinfunction "UART_DTR_46") (pintype "passive+no_connect"))
    )
    (net (code "99") (name "unconnected-(U8-UART_RTS-Pad25)") (class "Default")
      (node (ref "U8") (pin "25") (pinfunction "UART_RTS_25") (pintype "passive+no_connect"))
    )
    (net (code "100") (name "unconnected-(U8-UART_RXD-Pad23)") (class "Default")
      (node (ref "U8") (pin "23") (pinfunction "UART_RXD_23") (pintype "passive+no_connect"))
    )
    (net (code "101") (name "unconnected-(U8-UART_TXD-Pad31)") (class "Default")
      (node (ref "U8") (pin "31") (pinfunction "UART_TXD_31") (pintype "passive+no_connect"))
    )
    (net (code "102") (name "unconnected-(U8-USIM_PRESENCT-Pad44)") (class "Default")
      (node (ref "U8") (pin "44") (pinfunction "USIM_PRESENCT_44") (pintype "passive+no_connect"))
    )
    (net (code "103") (name "unconnected-(U8-WAKEUP_IN-Pad19)") (class "Default")
      (node (ref "U8") (pin "19") (pinfunction "WAKEUP_IN_19") (pintype "passive+no_connect"))
    )
    (net (code "104") (name "unconnected-(U8-WAKEUP_OUT-Pad32)") (class "Default")
      (node (ref "U8") (pin "32") (pinfunction "WAKEUP_OUT_32") (pintype "passive+no_connect"))
    )
    (net (code "105") (name "unconnected-(U8-W_DISABLE#-Pad20)") (class "Default")
      (node (ref "U8") (pin "20") (pinfunction "W_DISABLE#_20") (pintype "passive+no_connect"))
    )
    (net (code "106") (name "unconnected-(U10-GND-Pad15)") (class "Default")
      (node (ref "U10") (pin "15") (pinfunction "GND_15") (pintype "passive"))
    )
    (net (code "107") (name "unconnected-(U10-TEST{slash}SCL-Pad14)") (class "Default")
      (node (ref "U10") (pin "14") (pinfunction "TEST/SCL_14") (pintype "passive+no_connect"))
    )
    (net (code "108") (name "unconnected-(U10-~{OVCUR2}-Pad19)") (class "Default")
      (node (ref "U10") (pin "19") (pinfunction "~{OVCUR2}_19") (pintype "passive+no_connect"))
    )
    (net (code "109") (name "unconnected-(U10-~{PWREN1}-Pad22)") (class "Default")
      (node (ref "U10") (pin "22") (pinfunction "~{PWREN1}_22") (pintype "passive+no_connect"))
    )
    (net (code "110") (name "unconnected-(U10-~{PWREN2}-Pad20)") (class "Default")
      (node (ref "U10") (pin "20") (pinfunction "~{PWREN2}_20") (pintype "passive+no_connect"))
    )
    (net (code "111") (name "unconnected-(U11-NC-PadC4)") (class "Default")
      (node (ref "U11") (pin "C4") (pinfunction "NC_C4") (pintype "passive"))
    )
    (net (code "112") (name "unconnected-(U12-K2-Pad3)") (class "Default")
      (node (ref "U12") (pin "3") (pinfunction "K2_3") (pintype "passive+no_connect"))
    )
    (net (code "113") (name "unconnected-(U13-OUT3-Pad30)") (class "Default")
      (node (ref "U13") (pin "30") (pinfunction "OUT3_30") (pintype "passive+no_connect"))
    )
  )
)
